# sheet2_power.net
KiCad netlist of a schematic drawn in Altium Designer
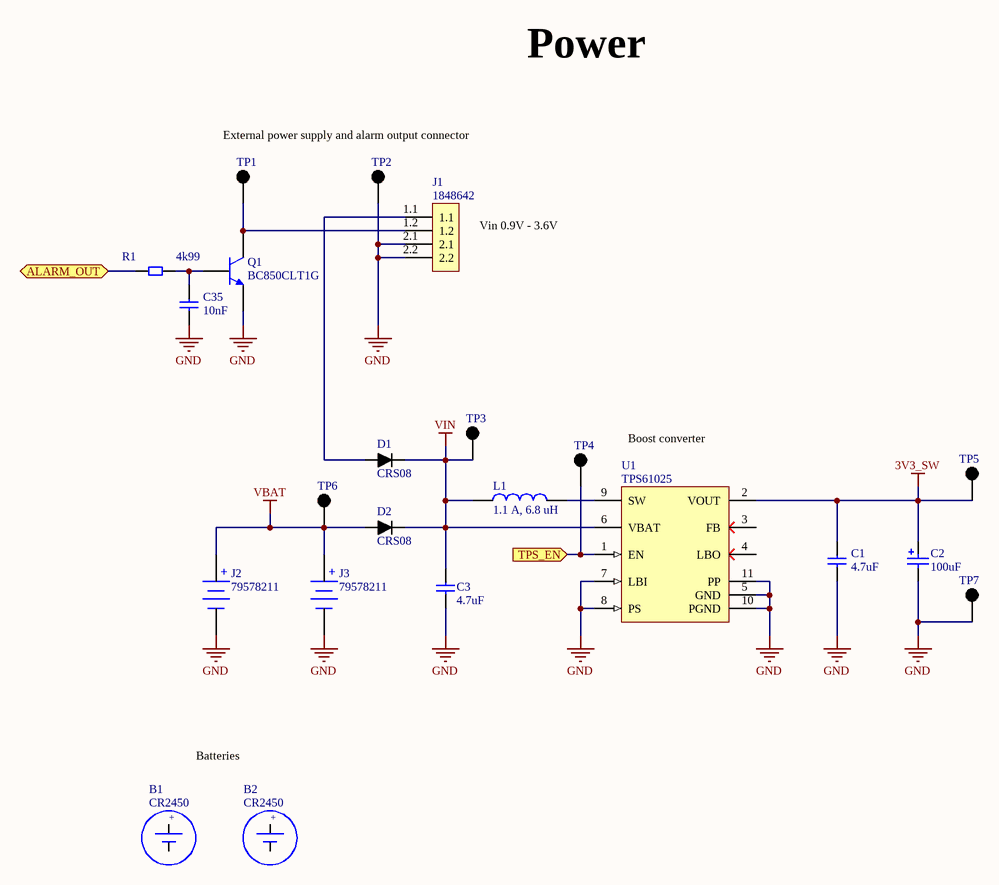
[diagram p0: sheet2_power.SchDoc]

(export (version "E")
  (design (tool "Eeschema 10.0.6"))
  (components
    (comp (ref "B1")
      (value "CR2450")
      (description "CR2450 Coin cell battery")
      (fields (field (name "MANUFACTURER") "Eve Energy"))
      (libsource (lib "Schlib") (part "Battery LCC 2450"))
    )
    (comp (ref "B2")
      (value "CR2450")
      (description "CR2450 Coin cell battery")
      (fields (field (name "MANUFACTURER") "Eve Energy"))
      (libsource (lib "Schlib") (part "Battery LCC 2450"))
    )
    (comp (ref "C1")
      (value "4.7uF")
      (footprint "CAP0603_GR18_MURATA")
      (description "Capacitor X5R 0603 Murata")
      (fields
        (field (name "MANUFACTURER") "Murata")
        (field (name "MANUFACTURER PART NUMBER") "GRM188R60J475KE19D")
      )
      (libsource (lib "Schlib") (part "CAP_0603_4u7"))
    )
    (comp (ref "C2")
      (value "100uF")
      (footprint "WCAP-PSHP_D10mm x L8.7mm")
      (description "WCAP-PSHP Aluminum Polymer Capacitors, D10mm x L8.7mm, 100 uF, 25 VDC")
      (fields
        (field (name "MANUFACTURER PART NUMBER") "875115560004")
        (field (name "MANUFACTURER") "Wurth Elektronik")
        (field (name "PUBLISHER") "Wurth Elektronik")
      )
      (libsource (lib "Schlib") (part "875115560004"))
    )
    (comp (ref "C3")
      (value "4.7uF")
      (footprint "CAP0603_GR18_MURATA")
      (description "Capacitor X5R 0603 Murata")
      (fields
        (field (name "MANUFACTURER") "Murata")
        (field (name "MANUFACTURER PART NUMBER") "GRM188R60J475KE19D")
      )
      (libsource (lib "Schlib") (part "CAP_0603_4u7"))
    )
    (comp (ref "C35")
      (value "10nF")
      (footprint "CAP0603_GCx18_MURATA")
      (description "Capacitor 0603 10nF")
      (fields
        (field (name "MANUFACTURER") "Murata")
        (field (name "MANUFACTURER PART NUMBER") "GCM188R72A103KA37D")
      )
      (libsource (lib "Schlib") (part "CAP_0603_10nF"))
    )
    (comp (ref "D1")
      (value "CRS08")
      (footprint "SOD-123F")
      (description "CRS08 Schottky Diode")
      (fields (field (name "MANUFACTURER") "Tohsiba"))
      (libsource (lib "Schlib") (part "CRS08 Schottky Diode"))
    )
    (comp (ref "D2")
      (value "CRS08")
      (footprint "SOD-123F")
      (description "CRS08 Schottky Diode")
      (fields (field (name "MANUFACTURER") "Tohsiba"))
      (libsource (lib "Schlib") (part "CRS08 Schottky Diode"))
    )
    (comp (ref "J1")
      (value "1848642")
      (footprint "Phoenix 1848642")
      (description "Plug component, Push-in spring connection")
      (fields (field (name "MANUFACTURER") "Phoenix Contact"))
      (libsource (lib "Schlib") (part "Phoenix Connector"))
    )
    (comp (ref "J2")
      (value "79578211")
      (footprint "79578211")
      (description "Battery Holder WA-BCPH, Battery Type: 2450p")
      (fields (field (name "MANUFACTURER") "Wurth Elektronik") (field (name "PUBLISHER") "Wurth Elektronik"))
      (libsource (lib "Schlib") (part "79578211"))
    )
    (comp (ref "J3")
      (value "79578211")
      (footprint "79578211")
      (description "Battery Holder WA-BCPH, Battery Type: 2450p")
      (fields (field (name "MANUFACTURER") "Wurth Elektronik") (field (name "PUBLISHER") "Wurth Elektronik"))
      (libsource (lib "Schlib") (part "79578211"))
    )
    (comp (ref "L1")
      (value "1.1 A, 6.8 uH")
      (footprint "WE-MAPI_3015")
      (description "WE-MAPI SMD Shielded Power Inductor, size 3015, 1.1 A, 6.8 uH")
      (fields
        (field (name "MANUFACTURER PART NUMBER") "74438335068")
        (field (name "MANUFACTURER") "Wurth Elektronik")
        (field (name "PUBLISHER") "Wurth Elektronik")
      )
      (libsource (lib "Schlib") (part "74438335068"))
    )
    (comp (ref "Q1")
      (value "BC850CLT1G")
      (footprint "SOT23")
      (description "NPN general purpose transistor")
      (fields
        (field (name "MANUFACTURER") "On Semiconductor")
        (field (name "MANUFACTURER PART NUMBER") "NSVBC850CLT1G")
      )
      (libsource (lib "Schlib") (part "BC850C"))
    )
    (comp (ref "R1")
      (value "4k99")
      (footprint "RES0603VISHAY")
      (description "SMD Resistor 4k99 0603")
      (fields
        (field (name "MANUFACTURER") "Vishay")
        (field (name "MANUFACTURER PART NUMBER") "CRCW06034K99FKTABC")
      )
      (libsource (lib "Schlib") (part "Resistor_4k99"))
    )
    (comp (ref "TP1")
      (value "testpad")
      (footprint "TestPad")
      (description "Signal probe pad")
      (libsource (lib "Schlib") (part "TestPad"))
    )
    (comp (ref "TP2")
      (value "testpad")
      (footprint "TestPad")
      (description "Signal probe pad")
      (libsource (lib "Schlib") (part "TestPad"))
    )
    (comp (ref "TP3")
      (value "testpad")
      (footprint "TestPad")
      (description "Signal probe pad")
      (libsource (lib "Schlib") (part "TestPad"))
    )
    (comp (ref "TP4")
      (value "testpad")
      (footprint "TestPad")
      (description "Signal probe pad")
      (libsource (lib "Schlib") (part "TestPad"))
    )
    (comp (ref "TP5")
      (value "testpad")
      (footprint "TestPad")
      (description "Signal probe pad")
      (libsource (lib "Schlib") (part "TestPad"))
    )
    (comp (ref "TP6")
      (value "testpad")
      (footprint "TestPad")
      (description "Signal probe pad")
      (libsource (lib "Schlib") (part "TestPad"))
    )
    (comp (ref "TP7")
      (value "testpad")
      (footprint "TestPad")
      (description "Signal probe pad")
      (libsource (lib "Schlib") (part "TestPad"))
    )
    (comp (ref "U1")
      (value "TPS61025")
      (footprint "DRC10-2400X1650TP")
      (fields
        (field (name "MANUFACTURER") "Texas Instruments")
        (field (name "MANUFACTURER PART NUMBER") "TPS61025DRCR")
      )
      (libsource (lib "Schlib") (part "TPS61025DRCR"))
    )
  )
  (nets
    (net (code "1") (name "/ALARM_OUT") (class "Default")
      (node (ref "R1") (pin "1") (pinfunction "1_1") (pintype "passive"))
    )
    (net (code "2") (name "/TPS_EN") (class "Default")
      (node (ref "TP4") (pin "1") (pinfunction "1_1") (pintype "passive"))
      (node (ref "U1") (pin "1") (pinfunction "EN_1") (pintype "input"))
    )
    (net (code "3") (name "3V3_SW") (class "Default")
      (node (ref "C1") (pin "2") (pinfunction "2_2") (pintype "passive"))
      (node (ref "C2") (pin "1") (pinfunction "P_1") (pintype "passive"))
      (node (ref "TP5") (pin "1") (pinfunction "1_1") (pintype "passive"))
      (node (ref "U1") (pin "2") (pinfunction "VOUT_2") (pintype "power_in"))
    )
    (net (code "4") (name "GND") (class "Default")
      (node (ref "C1") (pin "1") (pinfunction "1_1") (pintype "passive"))
      (node (ref "C2") (pin "2") (pinfunction "N_2") (pintype "passive"))
      (node (ref "C3") (pin "1") (pinfunction "1_1") (pintype "passive"))
      (node (ref "C35") (pin "1") (pinfunction "1_1") (pintype "passive"))
      (node (ref "J1") (pin "2.1") (pinfunction "2.1_2.1") (pintype "passive"))
      (node (ref "J1") (pin "2.2") (pinfunction "2.2_2.2") (pintype "passive"))
      (node (ref "J2") (pin "2") (pinfunction "Neg_2") (pintype "passive"))
      (node (ref "J3") (pin "2") (pinfunction "Neg_2") (pintype "passive"))
      (node (ref "Q1") (pin "2") (pinfunction "2_2") (pintype "passive"))
      (node (ref "TP2") (pin "1") (pinfunction "1_1") (pintype "passive"))
      (node (ref "TP7") (pin "1") (pinfunction "1_1") (pintype "passive"))
      (node (ref "U1") (pin "10") (pinfunction "PGND_10") (pintype "power_in"))
      (node (ref "U1") (pin "11") (pinfunction "PP_11") (pintype "power_in"))
      (node (ref "U1") (pin "5") (pinfunction "GND_5") (pintype "power_in"))
      (node (ref "U1") (pin "7") (pinfunction "LBI_7") (pintype "input"))
      (node (ref "U1") (pin "8") (pinfunction "PS_8") (pintype "input"))
    )
    (net (code "5") (name "Net-(C35-Pad2)") (class "Default")
      (node (ref "C35") (pin "2") (pinfunction "2_2") (pintype "passive"))
      (node (ref "Q1") (pin "1") (pinfunction "1_1") (pintype "passive"))
      (node (ref "R1") (pin "2") (pinfunction "2_2") (pintype "passive"))
    )
    (net (code "6") (name "Net-(D1-PadA)") (class "Default")
      (node (ref "D1") (pin "A") (pinfunction "A_A") (pintype "passive"))
      (node (ref "J1") (pin "1.1") (pinfunction "1.1_1.1") (pintype "passive"))
    )
    (net (code "7") (name "Net-(J1-Pad1.2)") (class "Default")
      (node (ref "J1") (pin "1.2") (pinfunction "1.2_1.2") (pintype "passive"))
      (node (ref "Q1") (pin "3") (pinfunction "3_3") (pintype "passive"))
      (node (ref "TP1") (pin "1") (pinfunction "1_1") (pintype "passive"))
    )
    (net (code "8") (name "Net-(U1-SW)") (class "Default")
      (node (ref "L1") (pin "2") (pinfunction "2_2") (pintype "passive"))
      (node (ref "U1") (pin "9") (pinfunction "SW_9") (pintype "power_in"))
    )
    (net (code "9") (name "VBAT") (class "Default")
      (node (ref "D2") (pin "A") (pinfunction "A_A") (pintype "passive"))
      (node (ref "J2") (pin "1") (pinfunction "Pos_1") (pintype "passive"))
      (node (ref "J3") (pin "1") (pinfunction "Pos_1") (pintype "passive"))
      (node (ref "TP6") (pin "1") (pinfunction "1_1") (pintype "passive"))
    )
    (net (code "10") (name "VIN") (class "Default")
      (node (ref "C3") (pin "2") (pinfunction "2_2") (pintype "passive"))
      (node (ref "D1") (pin "C") (pinfunction "C_C") (pintype "passive"))
      (node (ref "D2") (pin "C") (pinfunction "C_C") (pintype "passive"))
      (node (ref "L1") (pin "1") (pinfunction "1_1") (pintype "passive"))
      (node (ref "TP3") (pin "1") (pinfunction "1_1") (pintype "passive"))
      (node (ref "U1") (pin "6") (pinfunction "VBAT_6") (pintype "power_in"))
    )
    (net (code "11") (name "unconnected-(U1-FB-Pad3)") (class "Default")
      (node (ref "U1") (pin "3") (pinfunction "FB_3") (pintype "passive"))
    )
    (net (code "12") (name "unconnected-(U1-LBO-Pad4)") (class "Default")
      (node (ref "U1") (pin "4") (pinfunction "LBO_4") (pintype "tri_state"))
    )
  )
)
